# sensorHub.net
KiCad netlist of a schematic drawn in EAGLE
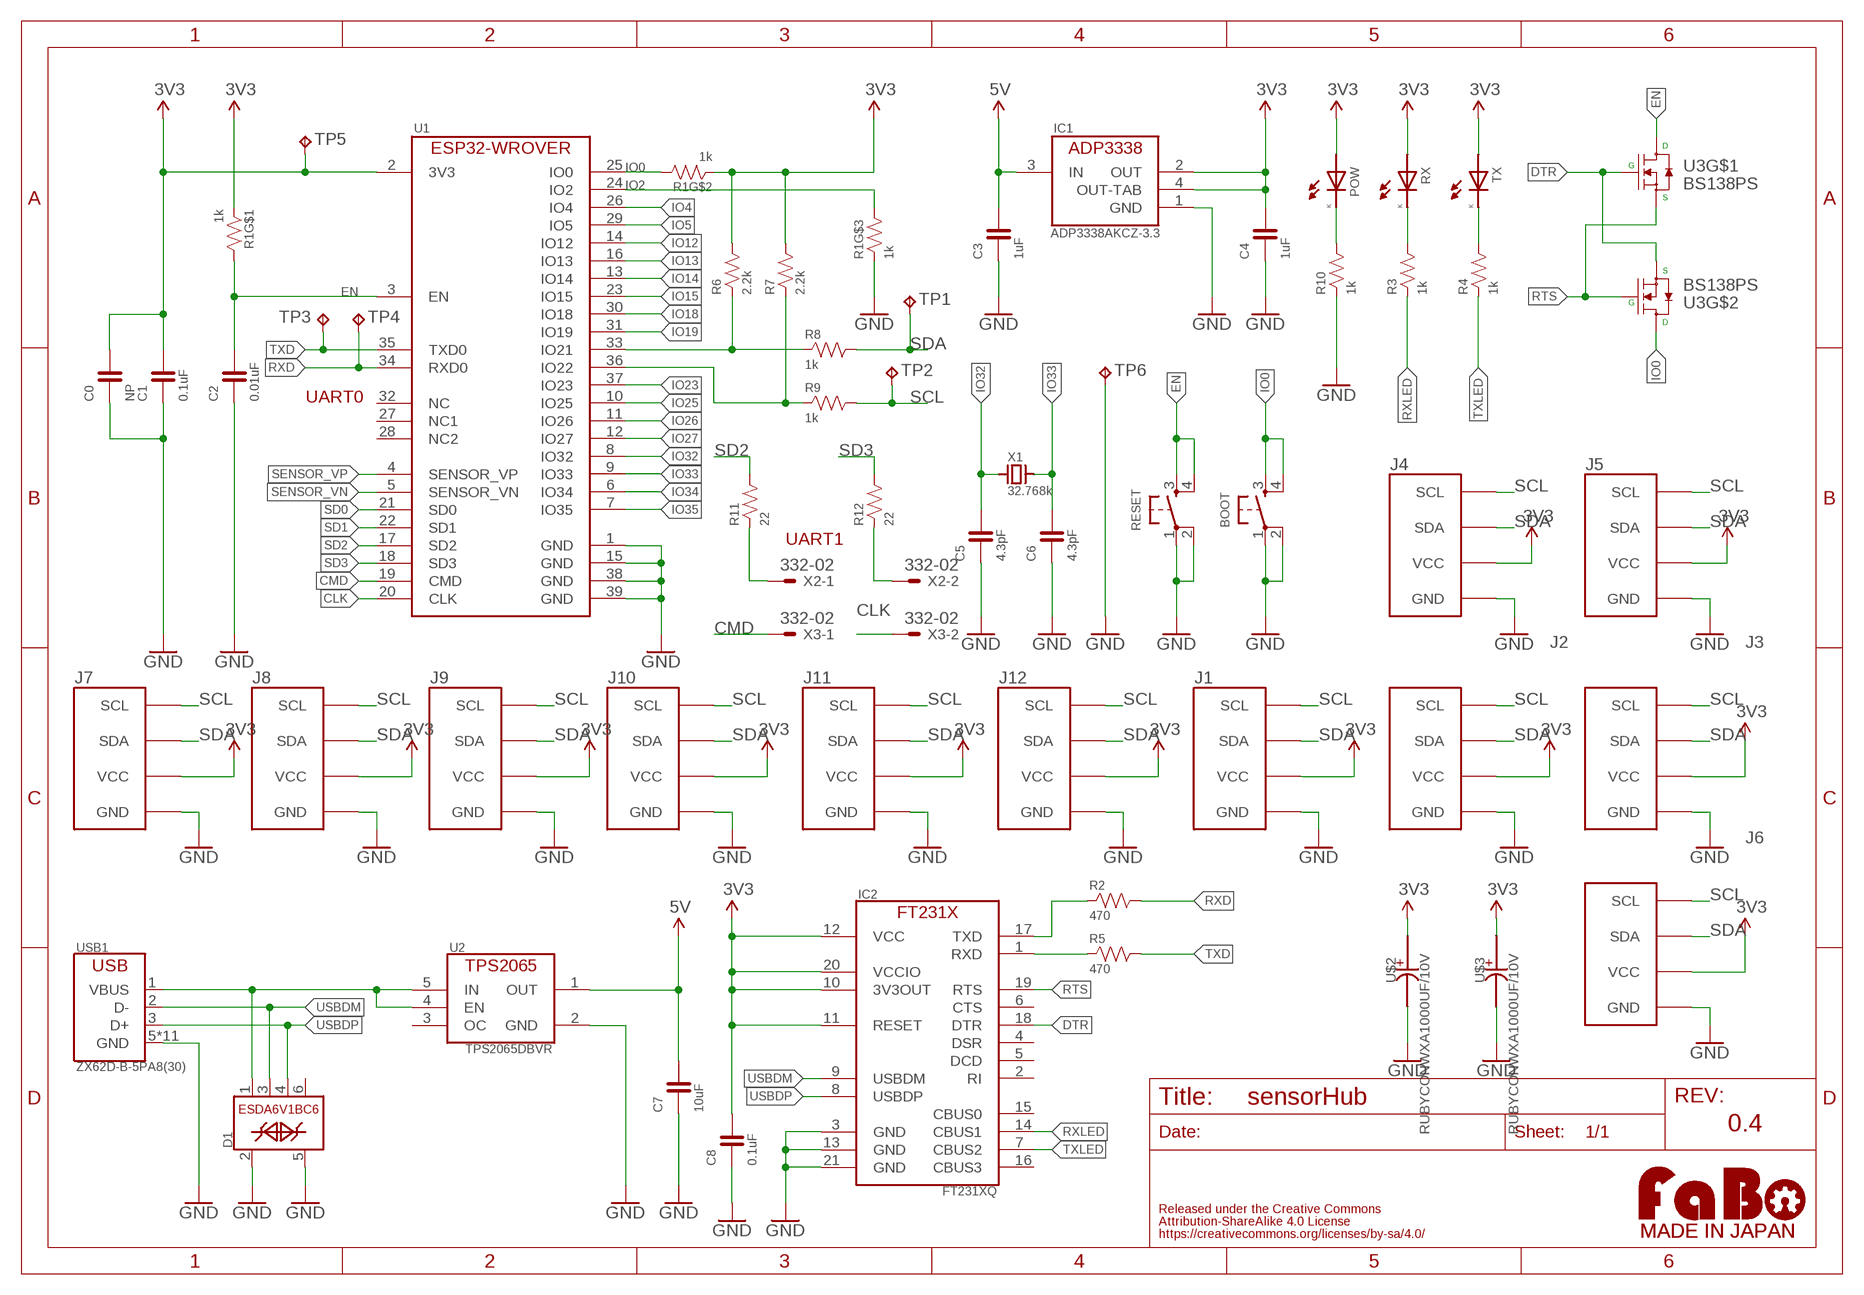
[diagram p0: schematic, sheet 1]

(export (version "E")
  (design (tool "Eeschema 10.0.6"))
  (components
    (comp (ref "BOOT")
      (value "TACTILE-KMR2")
      (footprint "eagle-import:KMR2-TACT")
      (libsource (lib "eagle-import") (part "TACTILE-KMR2"))
    )
    (comp (ref "C0")
      (value "NP")
      (footprint "eagle-import:MULTIPAD0603")
      (libsource (lib "eagle-import") (part "CAPACITOR-M"))
    )
    (comp (ref "C1")
      (value "0.1uF")
      (footprint "eagle-import:EIA0603")
      (libsource (lib "eagle-import") (part "CAPACITOR-0603"))
    )
    (comp (ref "C2")
      (value "0.01uF")
      (footprint "eagle-import:EIA0603")
      (libsource (lib "eagle-import") (part "CAPACITOR-0603"))
    )
    (comp (ref "C3")
      (value "1uF")
      (footprint "eagle-import:EIA0603")
      (libsource (lib "eagle-import") (part "CAPACITOR-0603"))
    )
    (comp (ref "C4")
      (value "1uF")
      (footprint "eagle-import:EIA0603")
      (libsource (lib "eagle-import") (part "CAPACITOR-0603"))
    )
    (comp (ref "C5")
      (value "4.3pF")
      (footprint "eagle-import:EIA0603")
      (libsource (lib "eagle-import") (part "CAPACITOR-0603"))
    )
    (comp (ref "C6")
      (value "4.3pF")
      (footprint "eagle-import:EIA0603")
      (libsource (lib "eagle-import") (part "CAPACITOR-0603"))
    )
    (comp (ref "C7")
      (value "10uF")
      (footprint "eagle-import:EIA0603")
      (libsource (lib "eagle-import") (part "CAPACITOR-0603"))
    )
    (comp (ref "C8")
      (value "0.1uF")
      (footprint "eagle-import:EIA0603")
      (libsource (lib "eagle-import") (part "CAPACITOR-0603"))
    )
    (comp (ref "D1")
      (value "ESDA6V1BC6")
      (footprint "eagle-import:SOT-23-6L")
      (libsource (lib "eagle-import") (part "ESDA6V1BC6"))
    )
    (comp (ref "IC1")
      (value "ADP3338AKCZ-3.3")
      (footprint "eagle-import:SOT-223-KC3")
      (libsource (lib "eagle-import") (part "ADP3338AKCZ"))
    )
    (comp (ref "IC2")
      (value "FT231XQ")
      (footprint "eagle-import:QFN-20")
      (libsource (lib "eagle-import") (part "FT231XQ"))
    )
    (comp (ref "J1")
      (value "FABO_BRICK_I2C-S04B-PASK-2")
      (footprint "eagle-import:FABO_BRICK_I2C_S04B-PASK-2")
      (libsource (lib "eagle-import") (part "FABO_BRICK_I2C-S04B-PASK-2"))
    )
    (comp (ref "J2")
      (value "FABO_BRICK_I2C-S04B-PASK-2")
      (footprint "eagle-import:FABO_BRICK_I2C_S04B-PASK-2")
      (libsource (lib "eagle-import") (part "FABO_BRICK_I2C-S04B-PASK-2"))
    )
    (comp (ref "J3")
      (value "FABO_BRICK_I2C-S04B-PASK-2")
      (footprint "eagle-import:FABO_BRICK_I2C_S04B-PASK-2")
      (libsource (lib "eagle-import") (part "FABO_BRICK_I2C-S04B-PASK-2"))
    )
    (comp (ref "J4")
      (value "FABO_BRICK_I2C-S04B-PASK-2")
      (footprint "eagle-import:FABO_BRICK_I2C_S04B-PASK-2")
      (libsource (lib "eagle-import") (part "FABO_BRICK_I2C-S04B-PASK-2"))
    )
    (comp (ref "J5")
      (value "FABO_BRICK_I2C-S04B-PASK-2")
      (footprint "eagle-import:FABO_BRICK_I2C_S04B-PASK-2")
      (libsource (lib "eagle-import") (part "FABO_BRICK_I2C-S04B-PASK-2"))
    )
    (comp (ref "J6")
      (value "FABO_BRICK_I2C-S04B-PASK-2")
      (footprint "eagle-import:FABO_BRICK_I2C_S04B-PASK-2")
      (libsource (lib "eagle-import") (part "FABO_BRICK_I2C-S04B-PASK-2"))
    )
    (comp (ref "J7")
      (value "FABO_BRICK_I2C-S04B-PASK-2")
      (footprint "eagle-import:FABO_BRICK_I2C_S04B-PASK-2")
      (libsource (lib "eagle-import") (part "FABO_BRICK_I2C-S04B-PASK-2"))
    )
    (comp (ref "J8")
      (value "FABO_BRICK_I2C-S04B-PASK-2")
      (footprint "eagle-import:FABO_BRICK_I2C_S04B-PASK-2")
      (libsource (lib "eagle-import") (part "FABO_BRICK_I2C-S04B-PASK-2"))
    )
    (comp (ref "J9")
      (value "FABO_BRICK_I2C-S04B-PASK-2")
      (footprint "eagle-import:FABO_BRICK_I2C_S04B-PASK-2")
      (libsource (lib "eagle-import") (part "FABO_BRICK_I2C-S04B-PASK-2"))
    )
    (comp (ref "J10")
      (value "FABO_BRICK_I2C-S04B-PASK-2")
      (footprint "eagle-import:FABO_BRICK_I2C_S04B-PASK-2")
      (libsource (lib "eagle-import") (part "FABO_BRICK_I2C-S04B-PASK-2"))
    )
    (comp (ref "J11")
      (value "FABO_BRICK_I2C-S04B-PASK-2")
      (footprint "eagle-import:FABO_BRICK_I2C_S04B-PASK-2")
      (libsource (lib "eagle-import") (part "FABO_BRICK_I2C-S04B-PASK-2"))
    )
    (comp (ref "J12")
      (value "FABO_BRICK_I2C-S04B-PASK-2")
      (footprint "eagle-import:FABO_BRICK_I2C_S04B-PASK-2")
      (libsource (lib "eagle-import") (part "FABO_BRICK_I2C-S04B-PASK-2"))
    )
    (comp (ref "LOGO1")
      (value "LOGO_FABO-M_BOTTOM")
      (footprint "eagle-import:LOGO_FABO_M_BOTTOM")
      (libsource (lib "eagle-import") (part "LOGO_FABO-M_BOTTOM"))
    )
    (comp (ref "POW")
      (value "LED-0603")
      (footprint "eagle-import:LED_0603")
      (libsource (lib "eagle-import") (part "LED-0603"))
    )
    (comp (ref "R1")
      (value "1k")
      (footprint "eagle-import:EXBV8V")
      (libsource (lib "eagle-import") (part "RESISTOR_ARRAY"))
    )
    (comp (ref "R2")
      (value "470")
      (footprint "eagle-import:EIA0603")
      (libsource (lib "eagle-import") (part "RESISTOR-0603"))
    )
    (comp (ref "R3")
      (value "1k")
      (footprint "eagle-import:EIA0603")
      (libsource (lib "eagle-import") (part "RESISTOR-0603"))
    )
    (comp (ref "R4")
      (value "1k")
      (footprint "eagle-import:EIA0603")
      (libsource (lib "eagle-import") (part "RESISTOR-0603"))
    )
    (comp (ref "R5")
      (value "470")
      (footprint "eagle-import:EIA0603")
      (libsource (lib "eagle-import") (part "RESISTOR-0603"))
    )
    (comp (ref "R6")
      (value "2.2k")
      (footprint "eagle-import:EIA0603")
      (libsource (lib "eagle-import") (part "RESISTOR-0603"))
    )
    (comp (ref "R7")
      (value "2.2k")
      (footprint "eagle-import:EIA0603")
      (libsource (lib "eagle-import") (part "RESISTOR-0603"))
    )
    (comp (ref "R8")
      (value "1k")
      (footprint "eagle-import:EIA0603")
      (libsource (lib "eagle-import") (part "RESISTOR-0603"))
    )
    (comp (ref "R9")
      (value "1k")
      (footprint "eagle-import:EIA0603")
      (libsource (lib "eagle-import") (part "RESISTOR-0603"))
    )
    (comp (ref "R10")
      (value "1k")
      (footprint "eagle-import:EIA0603")
      (libsource (lib "eagle-import") (part "RESISTOR-0603"))
    )
    (comp (ref "R11")
      (value "22")
      (footprint "eagle-import:EIA0603")
      (libsource (lib "eagle-import") (part "RESISTOR-0603"))
    )
    (comp (ref "R12")
      (value "22")
      (footprint "eagle-import:EIA0603")
      (libsource (lib "eagle-import") (part "RESISTOR-0603"))
    )
    (comp (ref "RESET")
      (value "TACTILE-KMR2")
      (footprint "eagle-import:KMR2-TACT")
      (libsource (lib "eagle-import") (part "TACTILE-KMR2"))
    )
    (comp (ref "RX")
      (value "LED-0603")
      (footprint "eagle-import:LED_0603")
      (libsource (lib "eagle-import") (part "LED-0603"))
    )
    (comp (ref "TP1")
      (value "TPB1,27")
      (footprint "eagle-import:B1,27")
      (libsource (lib "eagle-import") (part "TPB1,27"))
    )
    (comp (ref "TP2")
      (value "TPB1,27")
      (footprint "eagle-import:B1,27")
      (libsource (lib "eagle-import") (part "TPB1,27"))
    )
    (comp (ref "TP3")
      (value "TPB1,27")
      (footprint "eagle-import:B1,27")
      (libsource (lib "eagle-import") (part "TPB1,27"))
    )
    (comp (ref "TP4")
      (value "TPB1,27")
      (footprint "eagle-import:B1,27")
      (libsource (lib "eagle-import") (part "TPB1,27"))
    )
    (comp (ref "TP5")
      (value "TPB1,27")
      (footprint "eagle-import:B1,27")
      (libsource (lib "eagle-import") (part "TPB1,27"))
    )
    (comp (ref "TP6")
      (value "TPB1,27")
      (footprint "eagle-import:B1,27")
      (libsource (lib "eagle-import") (part "TPB1,27"))
    )
    (comp (ref "TX")
      (value "LED-0603")
      (footprint "eagle-import:LED_0603")
      (libsource (lib "eagle-import") (part "LED-0603"))
    )
    (comp (ref "U$2")
      (value "RUBYCONWXA1000UF/10V")
      (footprint "eagle-import:ALUMINUM10_9")
      (libsource (lib "eagle-import") (part "RUBYCONWXA1000UF/10V"))
    )
    (comp (ref "U$3")
      (value "RUBYCONWXA1000UF/10V")
      (footprint "eagle-import:ALUMINUM10_9")
      (libsource (lib "eagle-import") (part "RUBYCONWXA1000UF/10V"))
    )
    (comp (ref "U1")
      (value "ESP32-WROVER-B")
      (footprint "eagle-import:ESP32-WROVER-B")
      (libsource (lib "eagle-import") (part "ESP32-WROVER-B"))
    )
    (comp (ref "U2")
      (value "TPS2065DBVR")
      (footprint "eagle-import:SOT-23-5")
      (libsource (lib "eagle-import") (part "TPS2065DBV"))
    )
    (comp (ref "U3")
      (value "BS138PS")
      (footprint "eagle-import:SOT-363")
      (libsource (lib "eagle-import") (part "BS138PS"))
    )
    (comp (ref "USB1")
      (value "ZX62D-B-5PA8(30)")
      (footprint "eagle-import:ZX62D-B-5PA8")
      (libsource (lib "eagle-import") (part "USB-ZX62D"))
    )
    (comp (ref "X1")
      (value "32.768k")
      (footprint "eagle-import:ABS07")
      (libsource (lib "eagle-import") (part "CRYSTAL-ABS07"))
    )
    (comp (ref "X2")
      (value "332-02")
      (footprint "eagle-import:332-02")
      (libsource (lib "eagle-import") (part "332-02"))
    )
    (comp (ref "X3")
      (value "332-02")
      (footprint "eagle-import:332-02")
      (libsource (lib "eagle-import") (part "332-02"))
    )
  )
  (nets
    (net (code "1") (name "/IO2") (class "Default")
      (node (ref "R1") (pin "6") (pinfunction "2_6") (pintype "bidirectional"))
      (node (ref "U1") (pin "24") (pinfunction "IO2_24") (pintype "bidirectional"))
    )
    (net (code "2") (name "/SCL") (class "Default")
      (node (ref "J1") (pin "SCL") (pinfunction "SCL_SCL") (pintype "bidirectional"))
      (node (ref "J10") (pin "SCL") (pinfunction "SCL_SCL") (pintype "bidirectional"))
      (node (ref "J11") (pin "SCL") (pinfunction "SCL_SCL") (pintype "bidirectional"))
      (node (ref "J12") (pin "SCL") (pinfunction "SCL_SCL") (pintype "bidirectional"))
      (node (ref "J2") (pin "SCL") (pinfunction "SCL_SCL") (pintype "bidirectional"))
      (node (ref "J3") (pin "SCL") (pinfunction "SCL_SCL") (pintype "bidirectional"))
      (node (ref "J4") (pin "SCL") (pinfunction "SCL_SCL") (pintype "bidirectional"))
      (node (ref "J5") (pin "SCL") (pinfunction "SCL_SCL") (pintype "bidirectional"))
      (node (ref "J6") (pin "SCL") (pinfunction "SCL_SCL") (pintype "bidirectional"))
      (node (ref "J7") (pin "SCL") (pinfunction "SCL_SCL") (pintype "bidirectional"))
      (node (ref "J8") (pin "SCL") (pinfunction "SCL_SCL") (pintype "bidirectional"))
      (node (ref "J9") (pin "SCL") (pinfunction "SCL_SCL") (pintype "bidirectional"))
      (node (ref "R9") (pin "2") (pinfunction "2_2") (pintype "bidirectional"))
      (node (ref "TP2") (pin "TP") (pinfunction "TP_TP") (pintype "input"))
    )
    (net (code "3") (name "/SDA") (class "Default")
      (node (ref "J1") (pin "SDA") (pinfunction "SDA_SDA") (pintype "bidirectional"))
      (node (ref "J10") (pin "SDA") (pinfunction "SDA_SDA") (pintype "bidirectional"))
      (node (ref "J11") (pin "SDA") (pinfunction "SDA_SDA") (pintype "bidirectional"))
      (node (ref "J12") (pin "SDA") (pinfunction "SDA_SDA") (pintype "bidirectional"))
      (node (ref "J2") (pin "SDA") (pinfunction "SDA_SDA") (pintype "bidirectional"))
      (node (ref "J3") (pin "SDA") (pinfunction "SDA_SDA") (pintype "bidirectional"))
      (node (ref "J4") (pin "SDA") (pinfunction "SDA_SDA") (pintype "bidirectional"))
      (node (ref "J5") (pin "SDA") (pinfunction "SDA_SDA") (pintype "bidirectional"))
      (node (ref "J6") (pin "SDA") (pinfunction "SDA_SDA") (pintype "bidirectional"))
      (node (ref "J7") (pin "SDA") (pinfunction "SDA_SDA") (pintype "bidirectional"))
      (node (ref "J8") (pin "SDA") (pinfunction "SDA_SDA") (pintype "bidirectional"))
      (node (ref "J9") (pin "SDA") (pinfunction "SDA_SDA") (pintype "bidirectional"))
      (node (ref "R8") (pin "2") (pinfunction "2_2") (pintype "bidirectional"))
      (node (ref "TP1") (pin "TP") (pinfunction "TP_TP") (pintype "input"))
    )
    (net (code "4") (name "3V3") (class "Default")
      (node (ref "C0") (pin "2") (pinfunction "2_2") (pintype "passive"))
      (node (ref "C1") (pin "2") (pinfunction "2_2") (pintype "passive"))
      (node (ref "C4") (pin "2") (pinfunction "2_2") (pintype "passive"))
      (node (ref "C8") (pin "2") (pinfunction "2_2") (pintype "passive"))
      (node (ref "IC1") (pin "2") (pinfunction "OUT_2") (pintype "bidirectional"))
      (node (ref "IC1") (pin "4") (pinfunction "OUT-TAB_4") (pintype "bidirectional"))
      (node (ref "IC2") (pin "10") (pinfunction "3V3OUT_10") (pintype "bidirectional"))
      (node (ref "IC2") (pin "11") (pinfunction "RESET_11") (pintype "bidirectional"))
      (node (ref "IC2") (pin "12") (pinfunction "VCC_12") (pintype "bidirectional"))
      (node (ref "IC2") (pin "20") (pinfunction "VCCIO_20") (pintype "bidirectional"))
      (node (ref "J1") (pin "VCC") (pinfunction "VCC_VCC") (pintype "bidirectional"))
      (node (ref "J10") (pin "VCC") (pinfunction "VCC_VCC") (pintype "bidirectional"))
      (node (ref "J11") (pin "VCC") (pinfunction "VCC_VCC") (pintype "bidirectional"))
      (node (ref "J12") (pin "VCC") (pinfunction "VCC_VCC") (pintype "bidirectional"))
      (node (ref "J2") (pin "VCC") (pinfunction "VCC_VCC") (pintype "bidirectional"))
      (node (ref "J3") (pin "VCC") (pinfunction "VCC_VCC") (pintype "bidirectional"))
      (node (ref "J4") (pin "VCC") (pinfunction "VCC_VCC") (pintype "bidirectional"))
      (node (ref "J5") (pin "VCC") (pinfunction "VCC_VCC") (pintype "bidirectional"))
      (node (ref "J6") (pin "VCC") (pinfunction "VCC_VCC") (pintype "bidirectional"))
      (node (ref "J7") (pin "VCC") (pinfunction "VCC_VCC") (pintype "bidirectional"))
      (node (ref "J8") (pin "VCC") (pinfunction "VCC_VCC") (pintype "bidirectional"))
      (node (ref "J9") (pin "VCC") (pinfunction "VCC_VCC") (pintype "bidirectional"))
      (node (ref "POW") (pin "A") (pinfunction "ANODE_A") (pintype "passive"))
      (node (ref "R1") (pin "1") (pinfunction "1_1") (pintype "bidirectional"))
      (node (ref "R1") (pin "2") (pinfunction "1_2") (pintype "bidirectional"))
      (node (ref "R6") (pin "2") (pinfunction "2_2") (pintype "bidirectional"))
      (node (ref "R7") (pin "2") (pinfunction "2_2") (pintype "bidirectional"))
      (node (ref "RX") (pin "A") (pinfunction "ANODE_A") (pintype "passive"))
      (node (ref "TP5") (pin "TP") (pinfunction "TP_TP") (pintype "input"))
      (node (ref "TX") (pin "A") (pinfunction "ANODE_A") (pintype "passive"))
      (node (ref "U$2") (pin "PLUS") (pinfunction "+_PLUS") (pintype "passive"))
      (node (ref "U$3") (pin "PLUS") (pinfunction "+_PLUS") (pintype "passive"))
      (node (ref "U1") (pin "2") (pinfunction "3V3_2") (pintype "bidirectional"))
    )
    (net (code "5") (name "5V") (class "Default")
      (node (ref "C3") (pin "2") (pinfunction "2_2") (pintype "passive"))
      (node (ref "C7") (pin "2") (pinfunction "2_2") (pintype "passive"))
      (node (ref "IC1") (pin "3") (pinfunction "IN_3") (pintype "bidirectional"))
      (node (ref "U2") (pin "1") (pinfunction "OUT_1") (pintype "bidirectional"))
    )
    (net (code "6") (name "CLK") (class "Default")
      (node (ref "U1") (pin "20") (pinfunction "CLK_20") (pintype "bidirectional"))
      (node (ref "X3") (pin "2") (pinfunction "S_2") (pintype "passive"))
    )
    (net (code "7") (name "CMD") (class "Default")
      (node (ref "U1") (pin "19") (pinfunction "CMD_19") (pintype "bidirectional"))
      (node (ref "X3") (pin "1") (pinfunction "S_1") (pintype "passive"))
    )
    (net (code "8") (name "DTR") (class "Default")
      (node (ref "IC2") (pin "18") (pinfunction "DTR_18") (pintype "bidirectional"))
      (node (ref "U3") (pin "2") (pinfunction "G_2") (pintype "passive"))
      (node (ref "U3") (pin "4") (pinfunction "S_4") (pintype "passive"))
    )
    (net (code "9") (name "EN") (class "Default")
      (node (ref "C2") (pin "2") (pinfunction "2_2") (pintype "passive"))
      (node (ref "R1") (pin "8") (pinfunction "2_8") (pintype "bidirectional"))
      (node (ref "RESET") (pin "3") (pinfunction "3_3") (pintype "passive"))
      (node (ref "RESET") (pin "4") (pinfunction "4_4") (pintype "passive"))
      (node (ref "U1") (pin "3") (pinfunction "EN_3") (pintype "bidirectional"))
      (node (ref "U3") (pin "6") (pinfunction "D_6") (pintype "passive"))
    )
    (net (code "10") (name "GND") (class "Default")
      (node (ref "BOOT") (pin "1") (pinfunction "1_1") (pintype "passive"))
      (node (ref "BOOT") (pin "2") (pinfunction "2_2") (pintype "passive"))
      (node (ref "C0") (pin "1") (pinfunction "1_1") (pintype "passive"))
      (node (ref "C1") (pin "1") (pinfunction "1_1") (pintype "passive"))
      (node (ref "C2") (pin "1") (pinfunction "1_1") (pintype "passive"))
      (node (ref "C3") (pin "1") (pinfunction "1_1") (pintype "passive"))
      (node (ref "C4") (pin "1") (pinfunction "1_1") (pintype "passive"))
      (node (ref "C5") (pin "1") (pinfunction "1_1") (pintype "passive"))
      (node (ref "C6") (pin "1") (pinfunction "1_1") (pintype "passive"))
      (node (ref "C7") (pin "1") (pinfunction "1_1") (pintype "passive"))
      (node (ref "C8") (pin "1") (pinfunction "1_1") (pintype "passive"))
      (node (ref "D1") (pin "2") (pinfunction "2_2") (pintype "bidirectional"))
      (node (ref "D1") (pin "5") (pinfunction "5_5") (pintype "bidirectional"))
      (node (ref "IC1") (pin "1") (pinfunction "GND_1") (pintype "bidirectional"))
      (node (ref "IC2") (pin "13") (pinfunction "GND_13") (pintype "bidirectional"))
      (node (ref "IC2") (pin "21") (pinfunction "GND_21") (pintype "bidirectional"))
      (node (ref "IC2") (pin "3") (pinfunction "GND_3") (pintype "bidirectional"))
      (node (ref "J1") (pin "GND") (pinfunction "GND_GND") (pintype "bidirectional"))
      (node (ref "J10") (pin "GND") (pinfunction "GND_GND") (pintype "bidirectional"))
      (node (ref "J11") (pin "GND") (pinfunction "GND_GND") (pintype "bidirectional"))
      (node (ref "J12") (pin "GND") (pinfunction "GND_GND") (pintype "bidirectional"))
      (node (ref "J2") (pin "GND") (pinfunction "GND_GND") (pintype "bidirectional"))
      (node (ref "J3") (pin "GND") (pinfunction "GND_GND") (pintype "bidirectional"))
      (node (ref "J4") (pin "GND") (pinfunction "GND_GND") (pintype "bidirectional"))
      (node (ref "J5") (pin "GND") (pinfunction "GND_GND") (pintype "bidirectional"))
      (node (ref "J6") (pin "GND") (pinfunction "GND_GND") (pintype "bidirectional"))
      (node (ref "J7") (pin "GND") (pinfunction "GND_GND") (pintype "bidirectional"))
      (node (ref "J8") (pin "GND") (pinfunction "GND_GND") (pintype "bidirectional"))
      (node (ref "J9") (pin "GND") (pinfunction "GND_GND") (pintype "bidirectional"))
      (node (ref "R1") (pin "3") (pinfunction "1_3") (pintype "bidirectional"))
      (node (ref "R10") (pin "1") (pinfunction "1_1") (pintype "bidirectional"))
      (node (ref "RESET") (pin "1") (pinfunction "1_1") (pintype "passive"))
      (node (ref "RESET") (pin "2") (pinfunction "2_2") (pintype "passive"))
      (node (ref "TP6") (pin "TP") (pinfunction "TP_TP") (pintype "input"))
      (node (ref "U$2") (pin "MINUS") (pinfunction "-_MINUS") (pintype "passive"))
      (node (ref "U$3") (pin "MINUS") (pinfunction "-_MINUS") (pintype "passive"))
      (node (ref "U1") (pin "1") (pinfunction "GND_1") (pintype "bidirectional"))
      (node (ref "U1") (pin "15") (pinfunction "GND_15") (pintype "bidirectional"))
      (node (ref "U1") (pin "38") (pinfunction "GND_38") (pintype "bidirectional"))
      (node (ref "U1") (pin "39") (pinfunction "GND_39") (pintype "bidirectional"))
      (node (ref "U2") (pin "2") (pinfunction "GND_2") (pintype "bidirectional"))
      (node (ref "USB1") (pin "5") (pinfunction "GND_5") (pintype "bidirectional"))
      (node (ref "USB1") (pin "B1") (pinfunction "GND_B1") (pintype "bidirectional"))
      (node (ref "USB1") (pin "B2") (pinfunction "GND_B2") (pintype "bidirectional"))
      (node (ref "USB1") (pin "B3") (pinfunction "GND_B3") (pintype "bidirectional"))
      (node (ref "USB1") (pin "B4") (pinfunction "GND_B4") (pintype "bidirectional"))
      (node (ref "USB1") (pin "T1") (pinfunction "GND_T1") (pintype "bidirectional"))
      (node (ref "USB1") (pin "T2") (pinfunction "GND_T2") (pintype "bidirectional"))
      (node (ref "USB1") (pin "T3") (pinfunction "GND_T3") (pintype "bidirectional"))
      (node (ref "USB1") (pin "T4") (pinfunction "GND_T4") (pintype "bidirectional"))
      (node (ref "USB1") (pin "T5") (pinfunction "GND_T5") (pintype "bidirectional"))
      (node (ref "USB1") (pin "T6") (pinfunction "GND_T6") (pintype "bidirectional"))
    )
    (net (code "11") (name "IO0") (class "Default")
      (node (ref "BOOT") (pin "3") (pinfunction "3_3") (pintype "passive"))
      (node (ref "BOOT") (pin "4") (pinfunction "4_4") (pintype "passive"))
      (node (ref "R1") (pin "7") (pinfunction "2_7") (pintype "bidirectional"))
      (node (ref "U1") (pin "25") (pinfunction "IO0_25") (pintype "bidirectional"))
      (node (ref "U3") (pin "3") (pinfunction "D_3") (pintype "passive"))
    )
    (net (code "12") (name "IO4") (class "Default")
      (node (ref "U1") (pin "26") (pinfunction "IO4_26") (pintype "bidirectional"))
    )
    (net (code "13") (name "IO5") (class "Default")
      (node (ref "U1") (pin "29") (pinfunction "IO5_29") (pintype "bidirectional"))
    )
    (net (code "14") (name "IO12") (class "Default")
      (node (ref "U1") (pin "14") (pinfunction "IO12_14") (pintype "bidirectional"))
    )
    (net (code "15") (name "IO13") (class "Default")
      (node (ref "U1") (pin "16") (pinfunction "IO13_16") (pintype "bidirectional"))
    )
    (net (code "16") (name "IO14") (class "Default")
      (node (ref "U1") (pin "13") (pinfunction "IO14_13") (pintype "bidirectional"))
    )
    (net (code "17") (name "IO15") (class "Default")
      (node (ref "U1") (pin "23") (pinfunction "IO15_23") (pintype "bidirectional"))
    )
    (net (code "18") (name "IO18") (class "Default")
      (node (ref "U1") (pin "30") (pinfunction "IO18_30") (pintype "bidirectional"))
    )
    (net (code "19") (name "IO19") (class "Default")
      (node (ref "U1") (pin "31") (pinfunction "IO19_31") (pintype "bidirectional"))
    )
    (net (code "20") (name "IO23") (class "Default")
      (node (ref "U1") (pin "37") (pinfunction "IO23_37") (pintype "bidirectional"))
    )
    (net (code "21") (name "IO25") (class "Default")
      (node (ref "U1") (pin "10") (pinfunction "IO25_10") (pintype "bidirectional"))
    )
    (net (code "22") (name "IO26") (class "Default")
      (node (ref "U1") (pin "11") (pinfunction "IO26_11") (pintype "bidirectional"))
    )
    (net (code "23") (name "IO27") (class "Default")
      (node (ref "U1") (pin "12") (pinfunction "IO27_12") (pintype "bidirectional"))
    )
    (net (code "24") (name "IO32") (class "Default")
      (node (ref "C5") (pin "2") (pinfunction "2_2") (pintype "passive"))
      (node (ref "U1") (pin "8") (pinfunction "IO32_8") (pintype "bidirectional"))
      (node (ref "X1") (pin "1") (pinfunction "P$1_1") (pintype "bidirectional"))
    )
    (net (code "25") (name "IO33") (class "Default")
      (node (ref "C6") (pin "2") (pinfunction "2_2") (pintype "passive"))
      (node (ref "U1") (pin "9") (pinfunction "IO33_9") (pintype "bidirectional"))
      (node (ref "X1") (pin "2") (pinfunction "P$2_2") (pintype "bidirectional"))
    )
    (net (code "26") (name "IO34") (class "Default")
      (node (ref "U1") (pin "6") (pinfunction "IO34_6") (pintype "bidirectional"))
    )
    (net (code "27") (name "IO35") (class "Default")
      (node (ref "U1") (pin "7") (pinfunction "IO35_7") (pintype "bidirectional"))
    )
    (net (code "28") (name "Net-(IC2-RXD)") (class "Default")
      (node (ref "IC2") (pin "1") (pinfunction "RXD_1") (pintype "bidirectional"))
      (node (ref "R5") (pin "1") (pinfunction "1_1") (pintype "bidirectional"))
    )
    (net (code "29") (name "Net-(IC2-TXD)") (class "Default")
      (node (ref "IC2") (pin "17") (pinfunction "TXD_17") (pintype "bidirectional"))
      (node (ref "R2") (pin "1") (pinfunction "1_1") (pintype "bidirectional"))
    )
    (net (code "30") (name "Net-(POW-CATHODE)") (class "Default")
      (node (ref "POW") (pin "K") (pinfunction "CATHODE_K") (pintype "passive"))
      (node (ref "R10") (pin "2") (pinfunction "2_2") (pintype "bidirectional"))
    )
    (net (code "31") (name "Net-(RX-CATHODE)") (class "Default")
      (node (ref "R3") (pin "2") (pinfunction "2_2") (pintype "bidirectional"))
      (node (ref "RX") (pin "K") (pinfunction "CATHODE_K") (pintype "passive"))
    )
    (net (code "32") (name "Net-(TX-CATHODE)") (class "Default")
      (node (ref "R4") (pin "2") (pinfunction "2_2") (pintype "bidirectional"))
      (node (ref "TX") (pin "K") (pinfunction "CATHODE_K") (pintype "passive"))
    )
    (net (code "33") (name "Net-(U1-IO21)") (class "Default")
      (node (ref "R6") (pin "1") (pinfunction "1_1") (pintype "bidirectional"))
      (node (ref "R8") (pin "1") (pinfunction "1_1") (pintype "bidirectional"))
      (node (ref "U1") (pin "33") (pinfunction "IO21_33") (pintype "bidirectional"))
    )
    (net (code "34") (name "Net-(U1-IO22)") (class "Default")
      (node (ref "R7") (pin "1") (pinfunction "1_1") (pintype "bidirectional"))
      (node (ref "R9") (pin "1") (pinfunction "1_1") (pintype "bidirectional"))
      (node (ref "U1") (pin "36") (pinfunction "IO22_36") (pintype "bidirectional"))
    )
    (net (code "35") (name "Net-(U2-EN)") (class "Default")
      (node (ref "D1") (pin "1") (pinfunction "1_1") (pintype "bidirectional"))
      (node (ref "U2") (pin "4") (pinfunction "EN_4") (pintype "bidirectional"))
      (node (ref "U2") (pin "5") (pinfunction "IN_5") (pintype "bidirectional"))
      (node (ref "USB1") (pin "1") (pinfunction "VBUS_1") (pintype "bidirectional"))
    )
    (net (code "36") (name "Net-(X2A-S)") (class "Default")
      (node (ref "R11") (pin "1") (pinfunction "1_1") (pintype "bidirectional"))
      (node (ref "X2") (pin "1") (pinfunction "S_1") (pintype "passive"))
    )
    (net (code "37") (name "Net-(X2B-S)") (class "Default")
      (node (ref "R12") (pin "1") (pinfunction "1_1") (pintype "bidirectional"))
      (node (ref "X2") (pin "2") (pinfunction "S_2") (pintype "passive"))
    )
    (net (code "38") (name "RTS") (class "Default")
      (node (ref "IC2") (pin "19") (pinfunction "RTS_19") (pintype "bidirectional"))
      (node (ref "U3") (pin "1") (pinfunction "S_1") (pintype "passive"))
      (node (ref "U3") (pin "5") (pinfunction "G_5") (pintype "passive"))
    )
    (net (code "39") (name "RXD") (class "Default")
      (node (ref "R2") (pin "2") (pinfunction "2_2") (pintype "bidirectional"))
      (node (ref "TP4") (pin "TP") (pinfunction "TP_TP") (pintype "input"))
      (node (ref "U1") (pin "34") (pinfunction "RXD0_34") (pintype "bidirectional"))
    )
    (net (code "40") (name "RXLED") (class "Default")
      (node (ref "IC2") (pin "14") (pinfunction "CBUS1_14") (pintype "bidirectional"))
      (node (ref "R3") (pin "1") (pinfunction "1_1") (pintype "bidirectional"))
    )
    (net (code "41") (name "SD0") (class "Default")
      (node (ref "U1") (pin "21") (pinfunction "SD0_21") (pintype "bidirectional"))
    )
    (net (code "42") (name "SD1") (class "Default")
      (node (ref "U1") (pin "22") (pinfunction "SD1_22") (pintype "bidirectional"))
    )
    (net (code "43") (name "SD2") (class "Default")
      (node (ref "R11") (pin "2") (pinfunction "2_2") (pintype "bidirectional"))
      (node (ref "U1") (pin "17") (pinfunction "SD2_17") (pintype "bidirectional"))
    )
    (net (code "44") (name "SD3") (class "Default")
      (node (ref "R12") (pin "2") (pinfunction "2_2") (pintype "bidirectional"))
      (node (ref "U1") (pin "18") (pinfunction "SD3_18") (pintype "bidirectional"))
    )
    (net (code "45") (name "SENSOR_VN") (class "Default")
      (node (ref "U1") (pin "5") (pinfunction "SENSOR_VN_5") (pintype "bidirectional"))
    )
    (net (code "46") (name "SENSOR_VP") (class "Default")
      (node (ref "U1") (pin "4") (pinfunction "SENSOR_VP_4") (pintype "bidirectional"))
    )
    (net (code "47") (name "TXD") (class "Default")
      (node (ref "R5") (pin "2") (pinfunction "2_2") (pintype "bidirectional"))
      (node (ref "TP3") (pin "TP") (pinfunction "TP_TP") (pintype "input"))
      (node (ref "U1") (pin "35") (pinfunction "TXD0_35") (pintype "bidirectional"))
    )
    (net (code "48") (name "TXLED") (class "Default")
      (node (ref "IC2") (pin "7") (pinfunction "CBUS2_7") (pintype "bidirectional"))
      (node (ref "R4") (pin "1") (pinfunction "1_1") (pintype "bidirectional"))
    )
    (net (code "49") (name "USBDM") (class "Default")
      (node (ref "D1") (pin "3") (pinfunction "3_3") (pintype "bidirectional"))
      (node (ref "IC2") (pin "9") (pinfunction "USBDM_9") (pintype "bidirectional"))
      (node (ref "USB1") (pin "2") (pinfunction "D-_2") (pintype "bidirectional"))
    )
    (net (code "50") (name "USBDP") (class "Default")
      (node (ref "D1") (pin "4") (pinfunction "4_4") (pintype "bidirectional"))
      (node (ref "IC2") (pin "8") (pinfunction "USBDP_8") (pintype "bidirectional"))
      (node (ref "USB1") (pin "3") (pinfunction "D+_3") (pintype "bidirectional"))
    )
    (net (code "51") (name "unconnected-(D1-Pad6)") (class "Default")
      (node (ref "D1") (pin "6") (pinfunction "6_6") (pintype "bidirectional"))
    )
    (net (code "52") (name "unconnected-(IC2-CBUS0-Pad15)") (class "Default")
      (node (ref "IC2") (pin "15") (pinfunction "CBUS0_15") (pintype "bidirectional"))
    )
    (net (code "53") (name "unconnected-(IC2-CBUS3-Pad16)") (class "Default")
      (node (ref "IC2") (pin "16") (pinfunction "CBUS3_16") (pintype "bidirectional"))
    )
    (net (code "54") (name "unconnected-(IC2-CTS-Pad6)") (class "Default")
      (node (ref "IC2") (pin "6") (pinfunction "CTS_6") (pintype "bidirectional"))
    )
    (net (code "55") (name "unconnected-(IC2-DCD-Pad5)") (class "Default")
      (node (ref "IC2") (pin "5") (pinfunction "DCD_5") (pintype "bidirectional"))
    )
    (net (code "56") (name "unconnected-(IC2-DSR-Pad4)") (class "Default")
      (node (ref "IC2") (pin "4") (pinfunction "DSR_4") (pintype "bidirectional"))
    )
    (net (code "57") (name "unconnected-(IC2-RI-Pad2)") (class "Default")
      (node (ref "IC2") (pin "2") (pinfunction "RI_2") (pintype "bidirectional"))
    )
    (net (code "58") (name "unconnected-(U1-NC-Pad32)") (class "Default")
      (node (ref "U1") (pin "32") (pinfunction "NC_32") (pintype "bidirectional"))
    )
    (net (code "59") (name "unconnected-(U1-NC1-Pad27)") (class "Default")
      (node (ref "U1") (pin "27") (pinfunction "NC1_27") (pintype "bidirectional"))
    )
    (net (code "60") (name "unconnected-(U1-NC2-Pad28)") (class "Default")
      (node (ref "U1") (pin "28") (pinfunction "NC2_28") (pintype "bidirectional"))
    )
    (net (code "61") (name "unconnected-(U2-OC-Pad3)") (class "Default")
      (node (ref "U2") (pin "3") (pinfunction "OC_3") (pintype "bidirectional"))
    )
  )
)
